# SKAARDUINO_v4.net
KiCad netlist of a schematic drawn in EAGLE
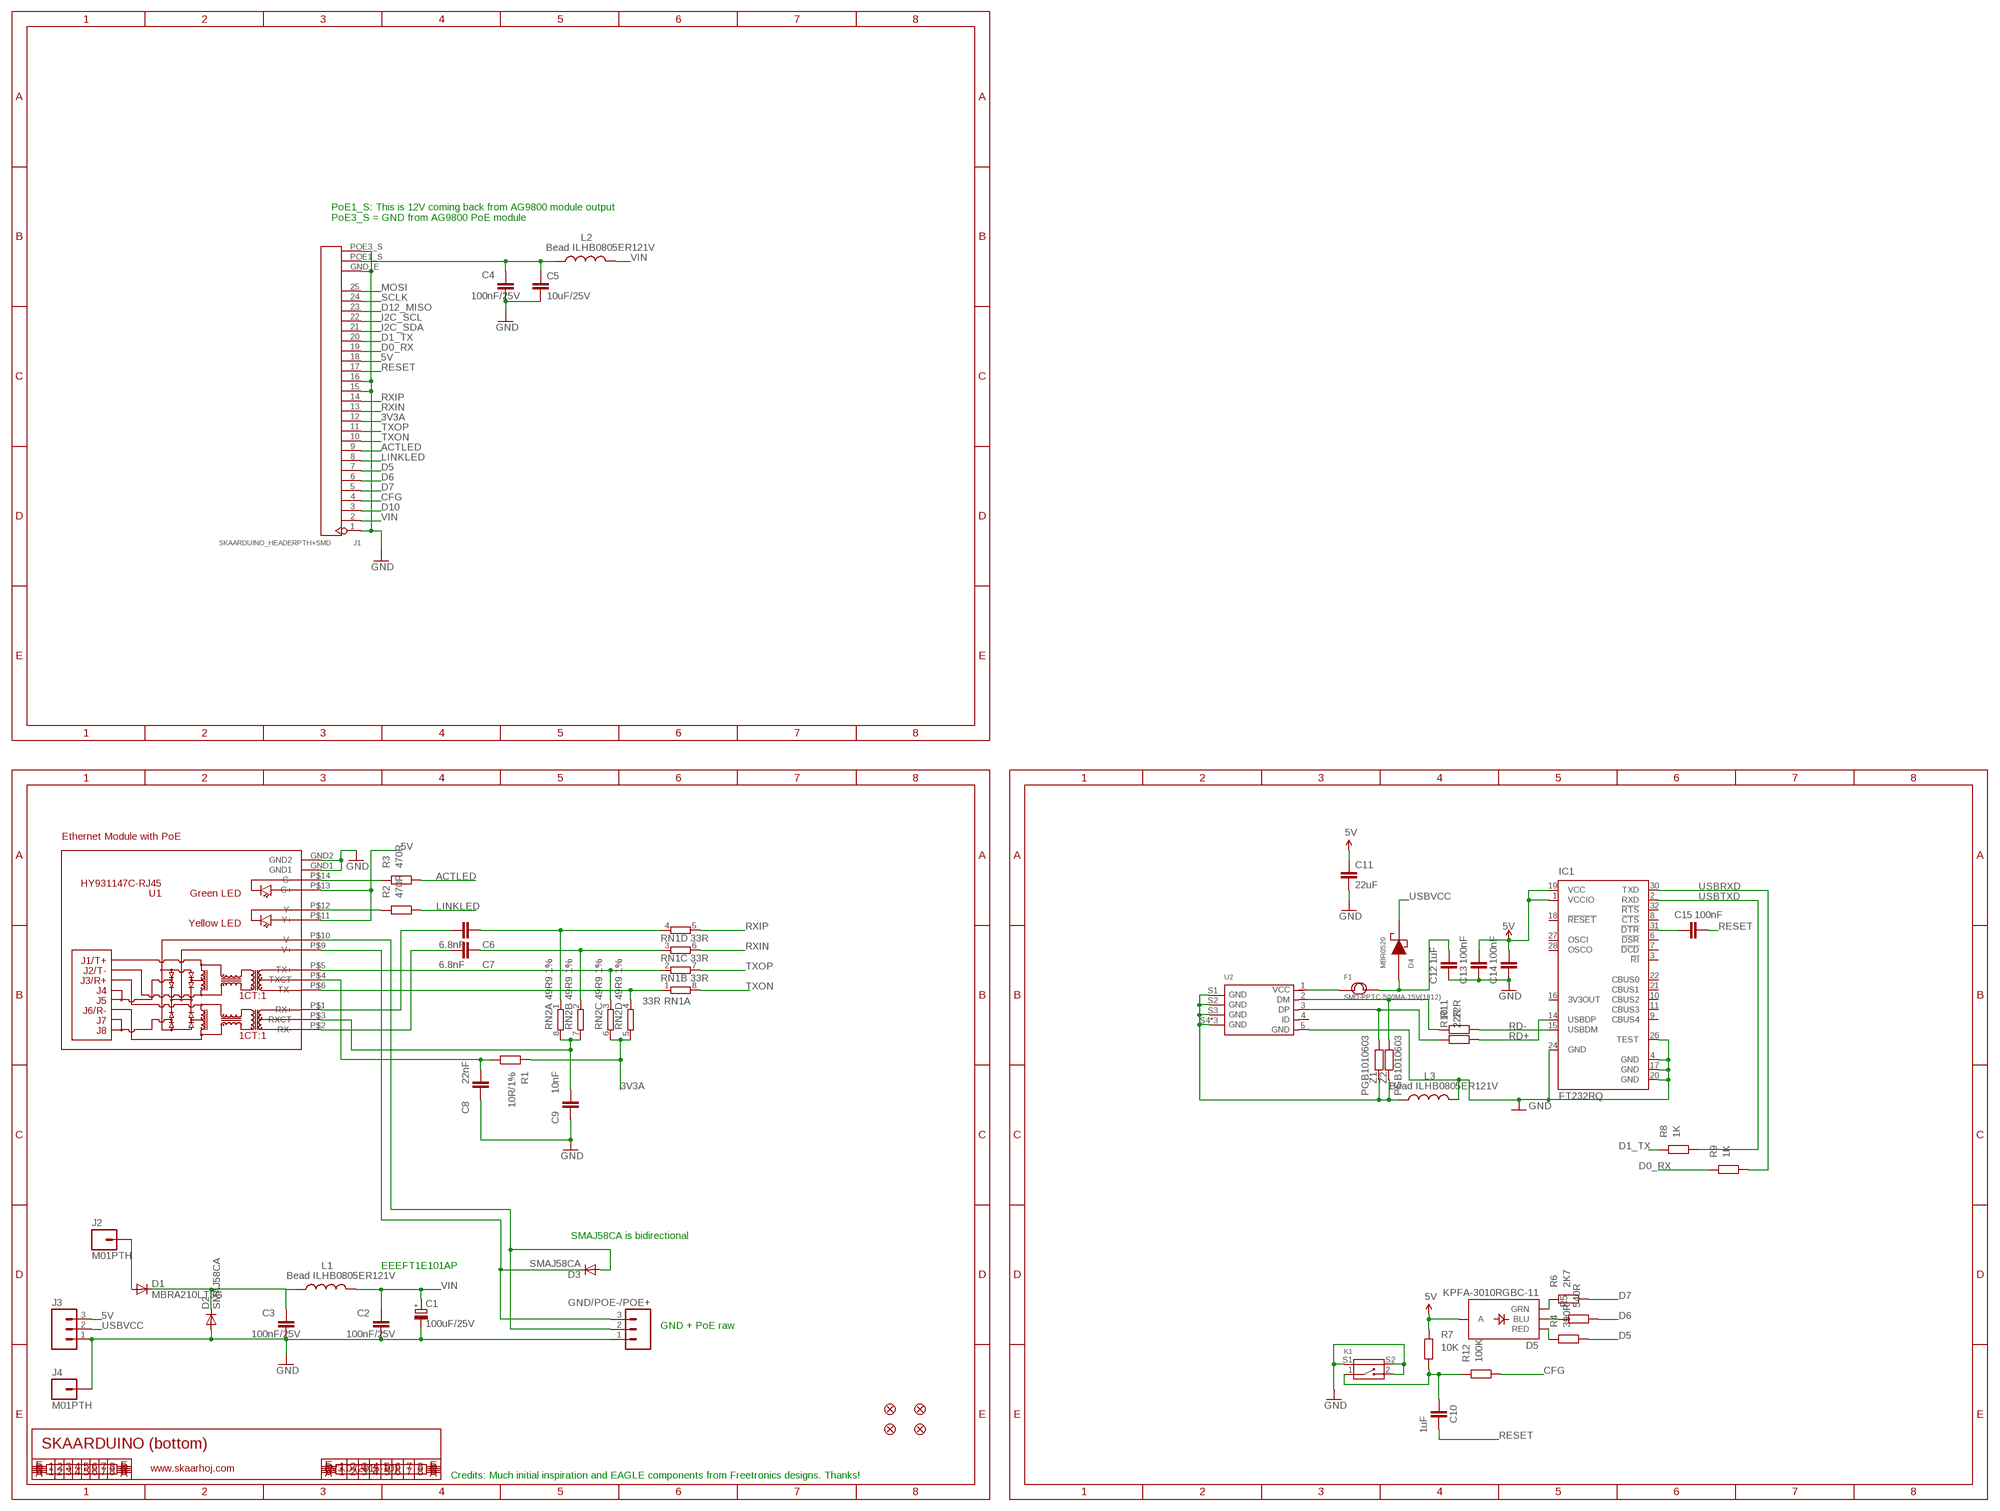
[diagram p0: schematic, sheet 1]
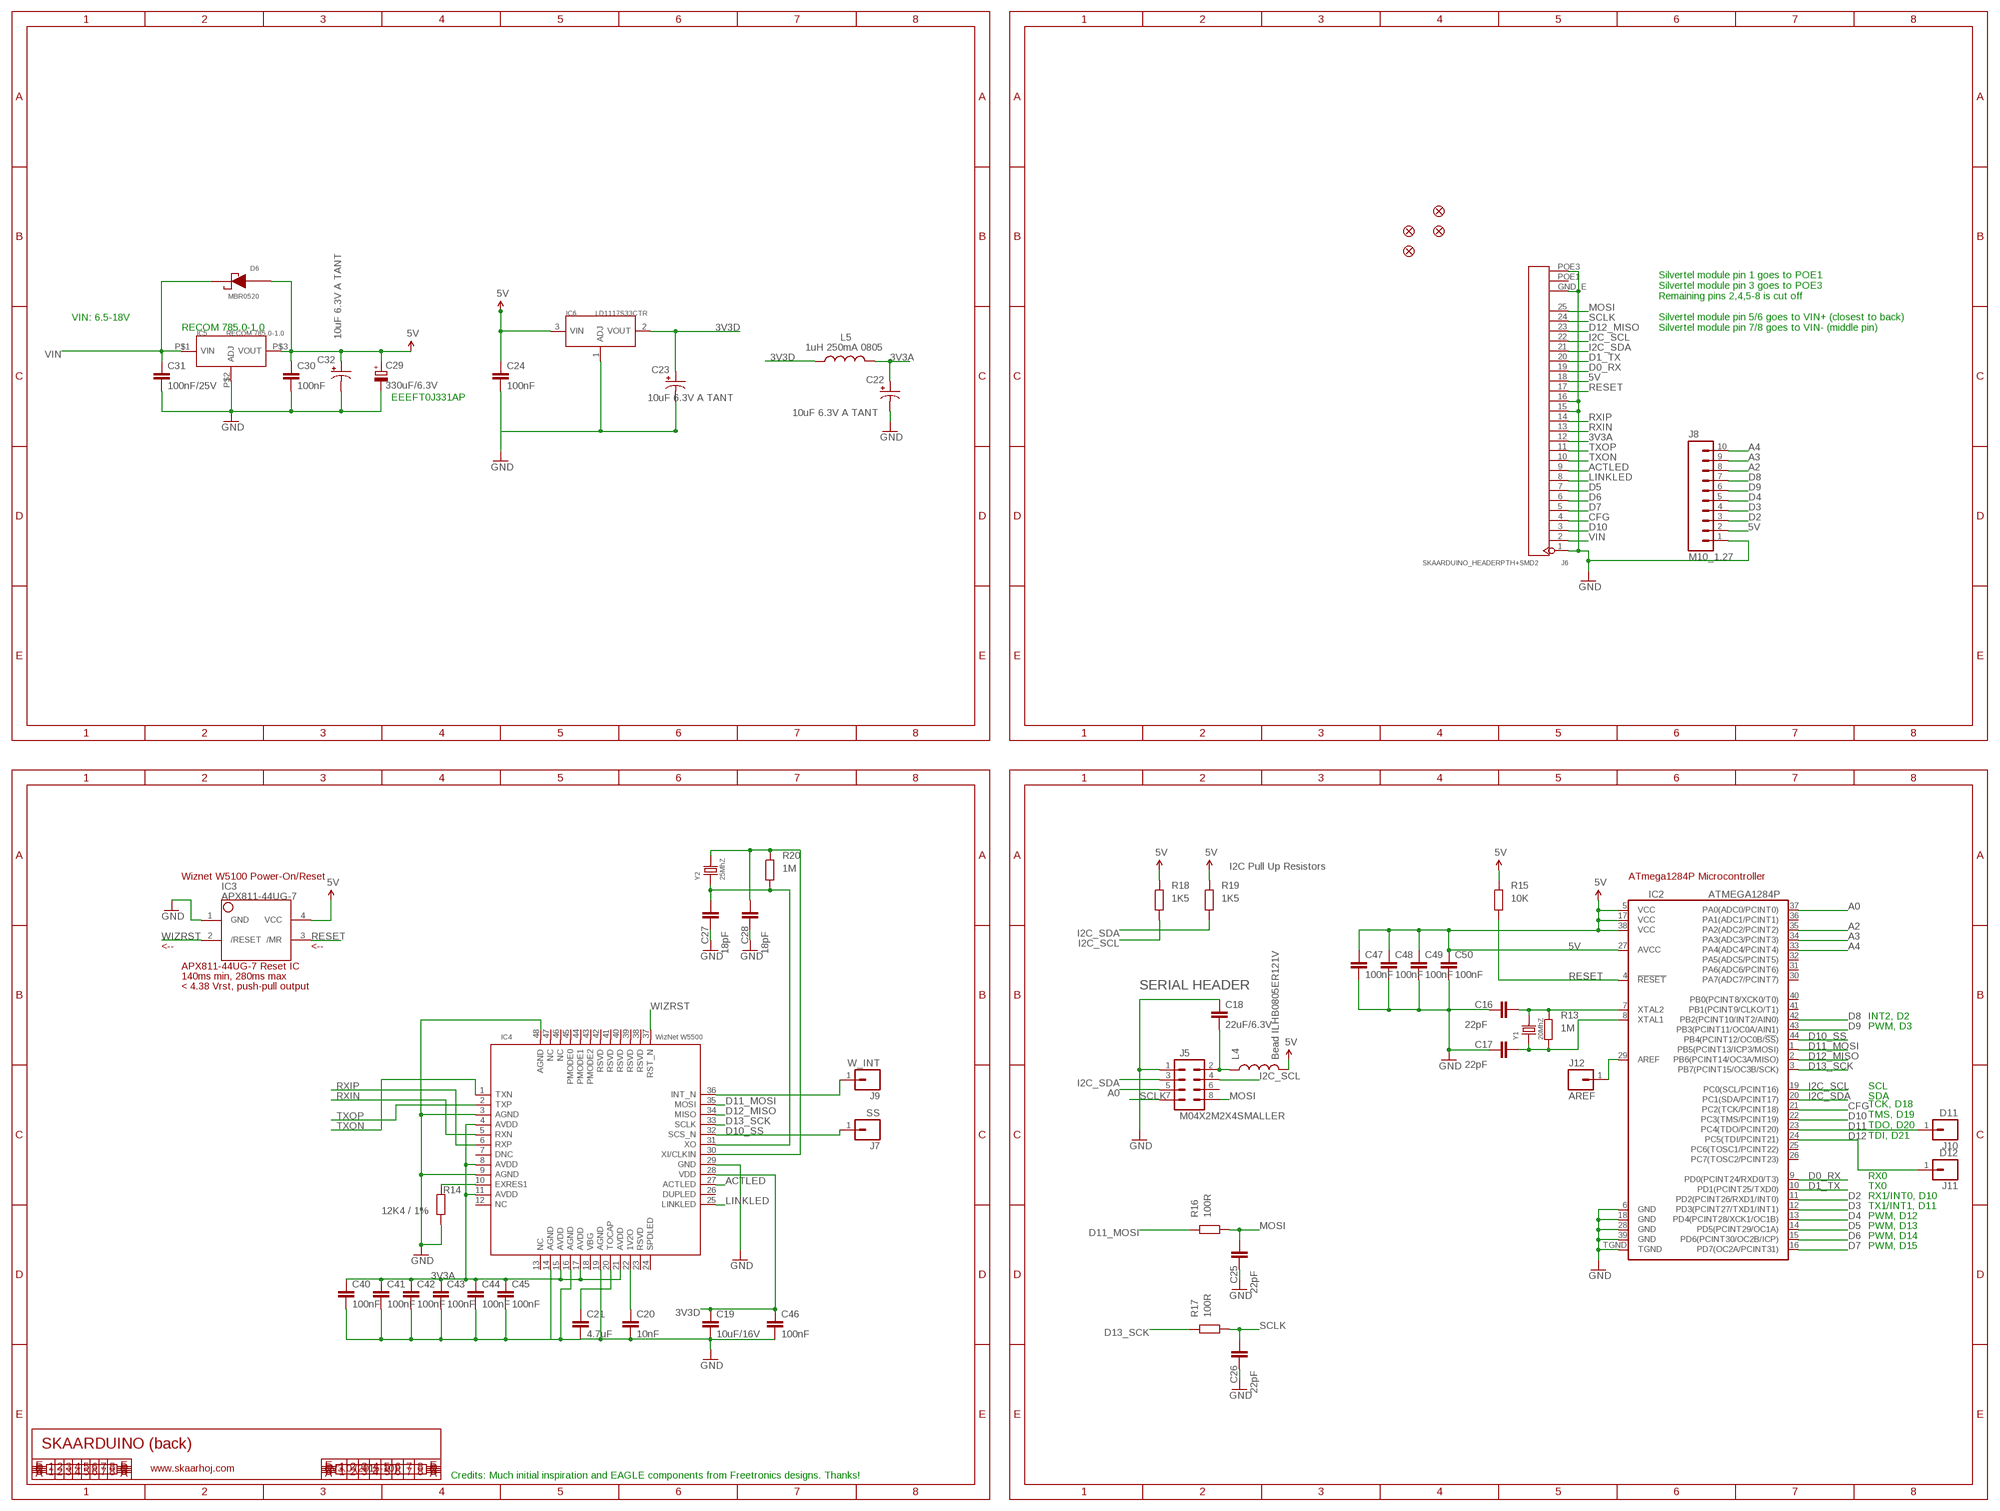
[diagram p1: schematic, sheet 2]

(export (version "E")
  (design (tool "Eeschema 10.0.6"))
  (components
    (comp (ref "C16")
      (value "22pF")
      (footprint "eagle-import:0402C")
      (libsource (lib "eagle-import") (part "C-EU0402C"))
    )
    (comp (ref "C17")
      (value "22pF")
      (footprint "eagle-import:0402C")
      (libsource (lib "eagle-import") (part "C-EU0402C"))
    )
    (comp (ref "C18")
      (value "22uF/6.3V")
      (footprint "eagle-import:0805")
      (libsource (lib "eagle-import") (part "CAP0805"))
    )
    (comp (ref "C19")
      (value "10uF/16V")
      (footprint "eagle-import:0805")
      (libsource (lib "eagle-import") (part "CAP0805"))
    )
    (comp (ref "C20")
      (value "10nF")
      (footprint "eagle-import:0402C")
      (libsource (lib "eagle-import") (part "C-EU0402C"))
    )
    (comp (ref "C21")
      (value "4.7uF")
      (footprint "eagle-import:0805")
      (libsource (lib "eagle-import") (part "CAP0805"))
    )
    (comp (ref "C22")
      (value "10uF 6.3V A TANT")
      (footprint "eagle-import:EIA3216")
      (libsource (lib "eagle-import") (part "CAP_POL1206"))
    )
    (comp (ref "C23")
      (value "10uF 6.3V A TANT")
      (footprint "eagle-import:EIA3216")
      (libsource (lib "eagle-import") (part "CAP_POL1206"))
    )
    (comp (ref "C24")
      (value "100nF")
      (footprint "eagle-import:0402C")
      (libsource (lib "eagle-import") (part "C-EU0402C"))
    )
    (comp (ref "C25")
      (value "22pF")
      (footprint "eagle-import:0402C")
      (libsource (lib "eagle-import") (part "C-EU0402C"))
    )
    (comp (ref "C26")
      (value "22pF")
      (footprint "eagle-import:0402C")
      (libsource (lib "eagle-import") (part "C-EU0402C"))
    )
    (comp (ref "C27")
      (value "18pF")
      (footprint "eagle-import:0402C")
      (libsource (lib "eagle-import") (part "C-EU0402C"))
    )
    (comp (ref "C28")
      (value "18pF")
      (footprint "eagle-import:0402C")
      (libsource (lib "eagle-import") (part "C-EU0402C"))
    )
    (comp (ref "C29")
      (value "330uF/6.3V")
      (footprint "eagle-import:PANASONIC_D")
      (libsource (lib "eagle-import") (part "CPOL-EUD"))
    )
    (comp (ref "C30")
      (value "100nF")
      (footprint "eagle-import:0402C")
      (libsource (lib "eagle-import") (part "C-EU0402C"))
    )
    (comp (ref "C31")
      (value "100nF/25V")
      (footprint "eagle-import:0402C")
      (libsource (lib "eagle-import") (part "C-EU0402C"))
    )
    (comp (ref "C32")
      (value "10uF 6.3V A TANT")
      (footprint "eagle-import:EIA3216")
      (libsource (lib "eagle-import") (part "CAP_POL1206"))
    )
    (comp (ref "C40")
      (value "100nF")
      (footprint "eagle-import:0402C")
      (libsource (lib "eagle-import") (part "C-EU0402C"))
    )
    (comp (ref "C41")
      (value "100nF")
      (footprint "eagle-import:0402C")
      (libsource (lib "eagle-import") (part "C-EU0402C"))
    )
    (comp (ref "C42")
      (value "100nF")
      (footprint "eagle-import:0402C")
      (libsource (lib "eagle-import") (part "C-EU0402C"))
    )
    (comp (ref "C43")
      (value "100nF")
      (footprint "eagle-import:0402C")
      (libsource (lib "eagle-import") (part "C-EU0402C"))
    )
    (comp (ref "C44")
      (value "100nF")
      (footprint "eagle-import:0402C")
      (libsource (lib "eagle-import") (part "C-EU0402C"))
    )
    (comp (ref "C45")
      (value "100nF")
      (footprint "eagle-import:0402C")
      (libsource (lib "eagle-import") (part "C-EU0402C"))
    )
    (comp (ref "C46")
      (value "100nF")
      (footprint "eagle-import:0402C")
      (libsource (lib "eagle-import") (part "C-EU0402C"))
    )
    (comp (ref "C47")
      (value "100nF")
      (footprint "eagle-import:0402C")
      (libsource (lib "eagle-import") (part "C-EU0402C"))
    )
    (comp (ref "C48")
      (value "100nF")
      (footprint "eagle-import:0402C")
      (libsource (lib "eagle-import") (part "C-EU0402C"))
    )
    (comp (ref "C49")
      (value "100nF")
      (footprint "eagle-import:0402C")
      (libsource (lib "eagle-import") (part "C-EU0402C"))
    )
    (comp (ref "C50")
      (value "100nF")
      (footprint "eagle-import:0402C")
      (libsource (lib "eagle-import") (part "C-EU0402C"))
    )
    (comp (ref "D6")
      (value "MBR0520")
      (footprint "eagle-import:SOD-123")
      (libsource (lib "eagle-import") (part "MBR0520"))
    )
    (comp (ref "FID5")
      (value "FIDUCIAL1X2.5")
      (footprint "eagle-import:FIDUCIAL-1X2.5")
      (libsource (lib "eagle-import") (part "FIDUCIAL1X2.5"))
    )
    (comp (ref "FID6")
      (value "FIDUCIAL1X2.5")
      (footprint "eagle-import:FIDUCIAL-1X2.5")
      (libsource (lib "eagle-import") (part "FIDUCIAL1X2.5"))
    )
    (comp (ref "FID7")
      (value "FIDUCIAL1X2.5")
      (footprint "eagle-import:FIDUCIAL-1X2.5")
      (libsource (lib "eagle-import") (part "FIDUCIAL1X2.5"))
    )
    (comp (ref "FID8")
      (value "FIDUCIAL1X2.5")
      (footprint "eagle-import:FIDUCIAL-1X2.5")
      (libsource (lib "eagle-import") (part "FIDUCIAL1X2.5"))
    )
    (comp (ref "IC2")
      (value "ATMEGA1284P")
      (footprint "eagle-import:QFN-44M1")
      (libsource (lib "eagle-import") (part "ATMEGA1284P"))
    )
    (comp (ref "IC3")
      (value "APX811-44UG-7")
      (footprint "eagle-import:SOT143-R")
      (libsource (lib "eagle-import") (part "APX81X-RESET-IC"))
    )
    (comp (ref "IC4")
      (value "WizNet W5500")
      (footprint "eagle-import:LQFP-48")
      (libsource (lib "eagle-import") (part "DRIVER-W5500"))
    )
    (comp (ref "IC5")
      (value "RECOM 785.0-1.0")
      (footprint "eagle-import:RECOM_785.0-1.0")
      (libsource (lib "eagle-import") (part "PMIC-LM317EMP"))
    )
    (comp (ref "IC6")
      (value "LD1117S33CTR")
      (footprint "eagle-import:SOT-223-UPRIGHT")
      (libsource (lib "eagle-import") (part "PMIC-LM317EMPUPRIGHT"))
    )
    (comp (ref "J5")
      (value "M04X2M2X4SMALLER")
      (footprint "eagle-import:M2X4SMALLER")
      (libsource (lib "eagle-import") (part "M04X2M2X4SMALLER"))
    )
    (comp (ref "J6")
      (value "SKAARDUINO_HEADERPTH+SMD2")
      (footprint "eagle-import:SKAARDUINO_PTH_SMD2_HEADER")
      (libsource (lib "eagle-import") (part "SKAARDUINO_HEADERPTH+SMD2"))
    )
    (comp (ref "J7")
      (value "SS")
      (footprint "eagle-import:M1X1")
      (libsource (lib "eagle-import") (part "M1X1TEST"))
    )
    (comp (ref "J8")
      (value "M10_1.27")
      (footprint "eagle-import:M10X1")
      (libsource (lib "eagle-import") (part "M10_1.27"))
    )
    (comp (ref "J9")
      (value "W_INT")
      (footprint "eagle-import:M1X1")
      (libsource (lib "eagle-import") (part "M1X1TEST"))
    )
    (comp (ref "J10")
      (value "D11")
      (footprint "eagle-import:M1X1")
      (libsource (lib "eagle-import") (part "M1X1TEST"))
    )
    (comp (ref "J11")
      (value "D12")
      (footprint "eagle-import:M1X1")
      (libsource (lib "eagle-import") (part "M1X1TEST"))
    )
    (comp (ref "J12")
      (value "AREF")
      (footprint "eagle-import:M1X1")
      (libsource (lib "eagle-import") (part "M1X1TEST"))
    )
    (comp (ref "L4")
      (value "Bead ILHB0805ER121V")
      (footprint "eagle-import:0805")
      (libsource (lib "eagle-import") (part "INDUCTOR0805"))
    )
    (comp (ref "L5")
      (value "1uH 250mA 0805")
      (footprint "eagle-import:L2012C")
      (libsource (lib "eagle-import") (part "L-USL2012C"))
    )
    (comp (ref "R13")
      (value "1M")
      (footprint "eagle-import:0402")
      (libsource (lib "eagle-import") (part "freetronics-jon_RESISTOR0402"))
    )
    (comp (ref "R14")
      (value "12K4 / 1%")
      (footprint "eagle-import:0402")
      (libsource (lib "eagle-import") (part "freetronics-jon_RESISTOR0402"))
    )
    (comp (ref "R15")
      (value "10K")
      (footprint "eagle-import:0402")
      (libsource (lib "eagle-import") (part "freetronics-jon_RESISTOR0402"))
    )
    (comp (ref "R16")
      (value "100R")
      (footprint "eagle-import:0402")
      (libsource (lib "eagle-import") (part "freetronics-jon_RESISTOR0402"))
    )
    (comp (ref "R17")
      (value "100R")
      (footprint "eagle-import:0402")
      (libsource (lib "eagle-import") (part "freetronics-jon_RESISTOR0402"))
    )
    (comp (ref "R18")
      (value "1K5")
      (footprint "eagle-import:0402")
      (libsource (lib "eagle-import") (part "freetronics-jon_RESISTOR0402"))
    )
    (comp (ref "R19")
      (value "1K5")
      (footprint "eagle-import:0402")
      (libsource (lib "eagle-import") (part "freetronics-jon_RESISTOR0402"))
    )
    (comp (ref "R20")
      (value "1M")
      (footprint "eagle-import:0402")
      (libsource (lib "eagle-import") (part "freetronics-jon_RESISTOR0402"))
    )
    (comp (ref "Y1")
      (value "20MhZ")
      (footprint "eagle-import:X2-SMD-5.0X3.2X1.3MM")
      (fields (field (name "MPN") "X053201602002"))
      (libsource (lib "eagle-import") (part "SMD-CRYSTAL-16MHZ-8PF-20PPM-40R(2P-5.0X3.2MM)"))
    )
    (comp (ref "Y2")
      (value "25MhZ")
      (footprint "eagle-import:X2-SMD-5.0X3.2X1.3MM")
      (fields (field (name "MPN") "X053201602002"))
      (libsource (lib "eagle-import") (part "SMD-CRYSTAL-16MHZ-8PF-20PPM-40R(2P-5.0X3.2MM)"))
    )
    (comp (ref "C1")
      (value "100uF/25V")
      (footprint "eagle-import:PANASONIC_D")
      (libsource (lib "eagle-import") (part "CPOL-EUD"))
    )
    (comp (ref "C2")
      (value "100nF/25V")
      (footprint "eagle-import:C0402")
      (libsource (lib "eagle-import") (part "CAP0402"))
    )
    (comp (ref "C3")
      (value "100nF/25V")
      (footprint "eagle-import:C0402")
      (libsource (lib "eagle-import") (part "CAP0402"))
    )
    (comp (ref "C4")
      (value "100nF/25V")
      (footprint "eagle-import:C0402")
      (libsource (lib "eagle-import") (part "CAP0402"))
    )
    (comp (ref "C5")
      (value "10uF/25V")
      (footprint "eagle-import:0805")
      (libsource (lib "eagle-import") (part "CAP0805"))
    )
    (comp (ref "C6")
      (value "6.8nF")
      (footprint "eagle-import:0402C")
      (libsource (lib "eagle-import") (part "C-EU0402C"))
    )
    (comp (ref "C7")
      (value "6.8nF")
      (footprint "eagle-import:0402C")
      (libsource (lib "eagle-import") (part "C-EU0402C"))
    )
    (comp (ref "C8")
      (value "22nF")
      (footprint "eagle-import:0402C")
      (libsource (lib "eagle-import") (part "C-EU0402C"))
    )
    (comp (ref "C9")
      (value "10nF")
      (footprint "eagle-import:0402C")
      (libsource (lib "eagle-import") (part "C-EU0402C"))
    )
    (comp (ref "C10")
      (value "1uF")
      (footprint "eagle-import:0402C")
      (libsource (lib "eagle-import") (part "C-EU0402C"))
    )
    (comp (ref "C11")
      (value "22uF")
      (footprint "eagle-import:0805")
      (libsource (lib "eagle-import") (part "CAP0805"))
    )
    (comp (ref "C12")
      (value "1uF")
      (footprint "eagle-import:0402C")
      (libsource (lib "eagle-import") (part "C-EU0402C"))
    )
    (comp (ref "C13")
      (value "100nF")
      (footprint "eagle-import:0402C")
      (libsource (lib "eagle-import") (part "C-EU0402C"))
    )
    (comp (ref "C14")
      (value "100nF")
      (footprint "eagle-import:0402C")
      (libsource (lib "eagle-import") (part "C-EU0402C"))
    )
    (comp (ref "C15")
      (value "100nF")
      (footprint "eagle-import:0402C")
      (libsource (lib "eagle-import") (part "C-EU0402C"))
    )
    (comp (ref "D1")
      (value "MBRA210LT3G")
      (footprint "eagle-import:SMA-DIODE")
      (libsource (lib "eagle-import") (part "DIODESMA"))
    )
    (comp (ref "D2")
      (value "SMAJ58CA")
      (footprint "eagle-import:SMA-DIODE")
      (libsource (lib "eagle-import") (part "DIODESMA"))
    )
    (comp (ref "D3")
      (value "SMAJ58CA")
      (footprint "eagle-import:SMA-DIODE")
      (libsource (lib "eagle-import") (part "DIODESMA"))
    )
    (comp (ref "D4")
      (value "MBR0520")
      (footprint "eagle-import:SOD-123")
      (libsource (lib "eagle-import") (part "MBR0520"))
    )
    (comp (ref "D5")
      (value "KPFA-3010RGBC-11")
      (footprint "eagle-import:LED-TRICOLOR-SMD")
      (libsource (lib "eagle-import") (part "LED-TRICOLOR"))
    )
    (comp (ref "F1")
      (value "SMD-PPTC-500MA-15V(1812)")
      (footprint "eagle-import:F1812")
      (libsource (lib "eagle-import") (part "SMD-PPTC-500MA-15V(1812)"))
    )
    (comp (ref "FID1")
      (value "FIDUCIAL1X2.5")
      (footprint "eagle-import:FIDUCIAL-1X2.5")
      (libsource (lib "eagle-import") (part "FIDUCIAL1X2.5"))
    )
    (comp (ref "FID2")
      (value "FIDUCIAL1X2.5")
      (footprint "eagle-import:FIDUCIAL-1X2.5")
      (libsource (lib "eagle-import") (part "FIDUCIAL1X2.5"))
    )
    (comp (ref "FID3")
      (value "FIDUCIAL1X2.5")
      (footprint "eagle-import:FIDUCIAL-1X2.5")
      (libsource (lib "eagle-import") (part "FIDUCIAL1X2.5"))
    )
    (comp (ref "FID4")
      (value "FIDUCIAL1X2.5")
      (footprint "eagle-import:FIDUCIAL-1X2.5")
      (libsource (lib "eagle-import") (part "FIDUCIAL1X2.5"))
    )
    (comp (ref "GND/POE-/POE+")
      (value "M03LOCK")
      (footprint "eagle-import:1X03_LOCK")
      (libsource (lib "eagle-import") (part "M03LOCK"))
    )
    (comp (ref "IC1")
      (value "FT232RQ")
      (footprint "eagle-import:QFN32")
      (libsource (lib "eagle-import") (part "FT232RQ"))
    )
    (comp (ref "J1")
      (value "SKAARDUINO_HEADERPTH+SMD")
      (footprint "eagle-import:SKAARDUINO_PTH_SMD_HEADER")
      (libsource (lib "eagle-import") (part "SKAARDUINO_HEADERPTH+SMD"))
    )
    (comp (ref "J2")
      (value "M01PTH")
      (footprint "eagle-import:1X01")
      (libsource (lib "eagle-import") (part "M01PTH"))
    )
    (comp (ref "J3")
      (value "M03LOCK")
      (footprint "eagle-import:1X03_LOCK")
      (libsource (lib "eagle-import") (part "M03LOCK"))
    )
    (comp (ref "J4")
      (value "M01PTH")
      (footprint "eagle-import:1X01")
      (libsource (lib "eagle-import") (part "M01PTH"))
    )
    (comp (ref "K1")
      (value "SMD-BUTTON-2+2P")
      (footprint "eagle-import:SW4-SMD-7.0X3.5X3.5MM-90D")
      (fields (field (name "MPN") "TS-1188E"))
      (libsource (lib "eagle-import") (part "SMD-BUTTON-2+2P"))
    )
    (comp (ref "L1")
      (value "Bead ILHB0805ER121V")
      (footprint "eagle-import:L2012C")
      (libsource (lib "eagle-import") (part "L-USL2012C"))
    )
    (comp (ref "L2")
      (value "Bead ILHB0805ER121V")
      (footprint "eagle-import:L2012C")
      (libsource (lib "eagle-import") (part "L-USL2012C"))
    )
    (comp (ref "L3")
      (value "Bead ILHB0805ER121V")
      (footprint "eagle-import:L2012C")
      (libsource (lib "eagle-import") (part "L-USL2012C"))
    )
    (comp (ref "R1")
      (value "10R/1%")
      (footprint "eagle-import:0402")
      (libsource (lib "eagle-import") (part "freetronics-jon_RESISTOR0402"))
    )
    (comp (ref "R2")
      (value "470R")
      (footprint "eagle-import:0402")
      (libsource (lib "eagle-import") (part "freetronics-jon_RESISTOR0402"))
    )
    (comp (ref "R3")
      (value "470R")
      (footprint "eagle-import:0402")
      (libsource (lib "eagle-import") (part "freetronics-jon_RESISTOR0402"))
    )
    (comp (ref "R4")
      (value "390R")
      (footprint "eagle-import:0402")
      (libsource (lib "eagle-import") (part "freetronics-jon_RESISTOR0402"))
    )
    (comp (ref "R5")
      (value "540R")
      (footprint "eagle-import:0402")
      (libsource (lib "eagle-import") (part "freetronics-jon_RESISTOR0402"))
    )
    (comp (ref "R6")
      (value "2K7")
      (footprint "eagle-import:0402")
      (libsource (lib "eagle-import") (part "freetronics-jon_RESISTOR0402"))
    )
    (comp (ref "R7")
      (value "10K")
      (footprint "eagle-import:0402")
      (libsource (lib "eagle-import") (part "freetronics-jon_RESISTOR0402"))
    )
    (comp (ref "R8")
      (value "1K")
      (footprint "eagle-import:0402")
      (libsource (lib "eagle-import") (part "freetronics-jon_RESISTOR0402"))
    )
    (comp (ref "R9")
      (value "1K")
      (footprint "eagle-import:0402")
      (libsource (lib "eagle-import") (part "freetronics-jon_RESISTOR0402"))
    )
    (comp (ref "R10")
      (value "22R")
      (footprint "eagle-import:0402")
      (libsource (lib "eagle-import") (part "freetronics-jon_RESISTOR0402"))
    )
    (comp (ref "R11")
      (value "22R")
      (footprint "eagle-import:0402")
      (libsource (lib "eagle-import") (part "freetronics-jon_RESISTOR0402"))
    )
    (comp (ref "R12")
      (value "100K")
      (footprint "eagle-import:0402")
      (libsource (lib "eagle-import") (part "freetronics-jon_RESISTOR0402"))
    )
    (comp (ref "RN1")
      (value "33R")
      (footprint "eagle-import:CAY16")
      (libsource (lib "eagle-import") (part "4R-NCAY16"))
    )
    (comp (ref "RN2")
      (value "49R9 1%")
      (footprint "eagle-import:CAY16")
      (libsource (lib "eagle-import") (part "4R-NCAY16"))
    )
    (comp (ref "U1")
      (value "HY931147C-RJ45")
      (footprint "eagle-import:HY931147C")
      (libsource (lib "eagle-import") (part "HY931147C-RJ45"))
    )
    (comp (ref "U2")
      (value "MICRO-USB-SMD-B-WITHOUT-POST-W/P(ST-USB-001G)")
      (footprint "eagle-import:MICRO-USB5+4P-SMD-0.65-B")
      (fields (field (name "MPN") "ST-USB-001G"))
      (libsource (lib "eagle-import") (part "MICRO-USB-SMD-B-WITHOUT-POST-W/P(ST-USB-001G)"))
    )
    (comp (ref "Z1")
      (value "PGB1010603")
      (footprint "eagle-import:C0402")
      (libsource (lib "eagle-import") (part "RESISTOR0402"))
    )
    (comp (ref "Z2")
      (value "PGB1010603")
      (footprint "eagle-import:C0402")
      (libsource (lib "eagle-import") (part "RESISTOR0402"))
    )
  )
  (nets
    (net (code "1") (name "3V3A") (class "Default")
      (node (ref "C22") (pin "A") (pinfunction "+_A") (pintype "passive"))
      (node (ref "C40") (pin "1") (pinfunction "1_1") (pintype "passive"))
      (node (ref "C41") (pin "1") (pinfunction "1_1") (pintype "passive"))
      (node (ref "C42") (pin "1") (pinfunction "1_1") (pintype "passive"))
      (node (ref "C43") (pin "1") (pinfunction "1_1") (pintype "passive"))
      (node (ref "C44") (pin "1") (pinfunction "1_1") (pintype "passive"))
      (node (ref "C45") (pin "1") (pinfunction "1_1") (pintype "passive"))
      (node (ref "IC4") (pin "11") (pinfunction "AVDD_11") (pintype "passive"))
      (node (ref "IC4") (pin "15") (pinfunction "AVDD_15") (pintype "passive"))
      (node (ref "IC4") (pin "17") (pinfunction "AVDD_17") (pintype "passive"))
      (node (ref "IC4") (pin "21") (pinfunction "AVDD_21") (pintype "passive"))
      (node (ref "IC4") (pin "4") (pinfunction "AVDD_4") (pintype "passive"))
      (node (ref "IC4") (pin "8") (pinfunction "AVDD_8") (pintype "passive"))
      (node (ref "J1") (pin "12") (pinfunction "12_12") (pintype "bidirectional"))
      (node (ref "J6") (pin "12") (pinfunction "12_12") (pintype "bidirectional"))
      (node (ref "L5") (pin "2") (pinfunction "2_2") (pintype "passive"))
      (node (ref "R1") (pin "2") (pinfunction "2_2") (pintype "passive"))
      (node (ref "RN2") (pin "5") (pinfunction "2_5") (pintype "passive"))
      (node (ref "RN2") (pin "6") (pinfunction "2_6") (pintype "passive"))
    )
    (net (code "2") (name "3V3D") (class "Default")
      (node (ref "C19") (pin "1") (pinfunction "1_1") (pintype "passive"))
      (node (ref "C23") (pin "A") (pinfunction "+_A") (pintype "passive"))
      (node (ref "C46") (pin "1") (pinfunction "1_1") (pintype "passive"))
      (node (ref "IC4") (pin "28") (pinfunction "VDD_28") (pintype "passive"))
      (node (ref "IC6") (pin "2") (pinfunction "VOUT_2") (pintype "bidirectional"))
      (node (ref "L5") (pin "1") (pinfunction "1_1") (pintype "passive"))
    )
    (net (code "3") (name "5V") (class "Default")
      (node (ref "C11") (pin "1") (pinfunction "1_1") (pintype "passive"))
      (node (ref "C13") (pin "2") (pinfunction "2_2") (pintype "passive"))
      (node (ref "C14") (pin "2") (pinfunction "2_2") (pintype "passive"))
      (node (ref "C24") (pin "1") (pinfunction "1_1") (pintype "passive"))
      (node (ref "C29") (pin "+") (pinfunction "+_+") (pintype "passive"))
      (node (ref "C30") (pin "1") (pinfunction "1_1") (pintype "passive"))
      (node (ref "C32") (pin "A") (pinfunction "+_A") (pintype "passive"))
      (node (ref "C47") (pin "1") (pinfunction "1_1") (pintype "passive"))
      (node (ref "C48") (pin "1") (pinfunction "1_1") (pintype "passive"))
      (node (ref "C49") (pin "1") (pinfunction "1_1") (pintype "passive"))
      (node (ref "C50") (pin "1") (pinfunction "1_1") (pintype "passive"))
      (node (ref "D5") (pin "A") (pinfunction "A_A") (pintype "bidirectional"))
      (node (ref "D6") (pin "2") (pinfunction "AN_2") (pintype "passive"))
      (node (ref "IC1") (pin "1") (pinfunction "VCCIO_1") (pintype "power_in"))
      (node (ref "IC1") (pin "19") (pinfunction "VCC_19") (pintype "power_in"))
      (node (ref "IC2") (pin "17") (pinfunction "VCC_17") (pintype "bidirectional"))
      (node (ref "IC2") (pin "27") (pinfunction "AVCC_27") (pintype "bidirectional"))
      (node (ref "IC2") (pin "38") (pinfunction "VCC_38") (pintype "bidirectional"))
      (node (ref "IC2") (pin "5") (pinfunction "VCC_5") (pintype "bidirectional"))
      (node (ref "IC3") (pin "4") (pinfunction "VCC_4") (pintype "power_in"))
      (node (ref "IC5") (pin "P$3") (pinfunction "VOUT_P$3") (pintype "bidirectional"))
      (node (ref "IC6") (pin "3") (pinfunction "VIN_3") (pintype "bidirectional"))
      (node (ref "J1") (pin "18") (pinfunction "18_18") (pintype "bidirectional"))
      (node (ref "J3") (pin "3") (pinfunction "3_3") (pintype "passive"))
      (node (ref "J6") (pin "18") (pinfunction "18_18") (pintype "bidirectional"))
      (node (ref "J8") (pin "2") (pinfunction "2_2") (pintype "passive"))
      (node (ref "L4") (pin "2") (pinfunction "2_2") (pintype "passive"))
      (node (ref "R15") (pin "2") (pinfunction "2_2") (pintype "passive"))
      (node (ref "R18") (pin "2") (pinfunction "2_2") (pintype "passive"))
      (node (ref "R19") (pin "2") (pinfunction "2_2") (pintype "passive"))
      (node (ref "R7") (pin "2") (pinfunction "2_2") (pintype "passive"))
      (node (ref "U1") (pin "P$11") (pinfunction "Y+_P$11") (pintype "bidirectional"))
      (node (ref "U1") (pin "P$13") (pinfunction "G+_P$13") (pintype "bidirectional"))
    )
    (net (code "4") (name "A0") (class "Default")
      (node (ref "IC2") (pin "37") (pinfunction "PA0(ADC0/PCINT0)_37") (pintype "bidirectional"))
      (node (ref "J5") (pin "5") (pinfunction "5_5") (pintype "passive"))
    )
    (net (code "5") (name "A2") (class "Default")
      (node (ref "IC2") (pin "35") (pinfunction "PA2(ADC2/PCINT2)_35") (pintype "bidirectional"))
      (node (ref "J8") (pin "8") (pinfunction "8_8") (pintype "passive"))
    )
    (net (code "6") (name "A3") (class "Default")
      (node (ref "IC2") (pin "34") (pinfunction "PA3(ADC3/PCINT3)_34") (pintype "bidirectional"))
      (node (ref "J8") (pin "9") (pinfunction "9_9") (pintype "passive"))
    )
    (net (code "7") (name "A4") (class "Default")
      (node (ref "IC2") (pin "33") (pinfunction "PA4(ADC4/PCINT4)_33") (pintype "bidirectional"))
      (node (ref "J8") (pin "10") (pinfunction "10_10") (pintype "passive"))
    )
    (net (code "8") (name "ACTLED") (class "Default")
      (node (ref "IC4") (pin "27") (pinfunction "ACTLED_27") (pintype "passive"))
      (node (ref "J1") (pin "9") (pinfunction "9_9") (pintype "bidirectional"))
      (node (ref "J6") (pin "9") (pinfunction "9_9") (pintype "bidirectional"))
      (node (ref "R3") (pin "1") (pinfunction "1_1") (pintype "passive"))
    )
    (net (code "9") (name "CFG") (class "Default")
      (node (ref "IC2") (pin "21") (pinfunction "PC2(TCK/PCINT18)_21") (pintype "bidirectional"))
      (node (ref "J1") (pin "4") (pinfunction "4_4") (pintype "bidirectional"))
      (node (ref "J6") (pin "4") (pinfunction "4_4") (pintype "bidirectional"))
      (node (ref "R12") (pin "1") (pinfunction "1_1") (pintype "passive"))
    )
    (net (code "10") (name "D0_RX") (class "Default")
      (node (ref "IC2") (pin "9") (pinfunction "PD0(PCINT24/RXD0/T3)_9") (pintype "bidirectional"))
      (node (ref "J1") (pin "19") (pinfunction "19_19") (pintype "bidirectional"))
      (node (ref "J6") (pin "19") (pinfunction "19_19") (pintype "bidirectional"))
      (node (ref "R9") (pin "2") (pinfunction "2_2") (pintype "passive"))
    )
    (net (code "11") (name "D1_TX") (class "Default")
      (node (ref "IC2") (pin "10") (pinfunction "PD1(PCINT25/TXD0)_10") (pintype "bidirectional"))
      (node (ref "J1") (pin "20") (pinfunction "20_20") (pintype "bidirectional"))
      (node (ref "J6") (pin "20") (pinfunction "20_20") (pintype "bidirectional"))
      (node (ref "R8") (pin "2") (pinfunction "2_2") (pintype "passive"))
    )
    (net (code "12") (name "D2") (class "Default")
      (node (ref "IC2") (pin "11") (pinfunction "PD2(PCINT26/RXD1/INT0)_11") (pintype "bidirectional"))
      (node (ref "J8") (pin "3") (pinfunction "3_3") (pintype "passive"))
    )
    (net (code "13") (name "D3") (class "Default")
      (node (ref "IC2") (pin "12") (pinfunction "PD3(PCINT27/TXD1/INT1)_12") (pintype "bidirectional"))
      (node (ref "J8") (pin "4") (pinfunction "4_4") (pintype "passive"))
    )
    (net (code "14") (name "D4") (class "Default")
      (node (ref "IC2") (pin "13") (pinfunction "PD4(PCINT28/XCK1/OC1B)_13") (pintype "bidirectional"))
      (node (ref "J8") (pin "5") (pinfunction "5_5") (pintype "passive"))
    )
    (net (code "15") (name "D5") (class "Default")
      (node (ref "IC2") (pin "14") (pinfunction "PD5(PCINT29/OC1A)_14") (pintype "bidirectional"))
      (node (ref "J1") (pin "7") (pinfunction "7_7") (pintype "bidirectional"))
      (node (ref "J6") (pin "7") (pinfunction "7_7") (pintype "bidirectional"))
      (node (ref "R4") (pin "1") (pinfunction "1_1") (pintype "passive"))
    )
    (net (code "16") (name "D6") (class "Default")
      (node (ref "IC2") (pin "15") (pinfunction "PD6(PCINT30/OC2B/ICP)_15") (pintype "bidirectional"))
      (node (ref "J1") (pin "6") (pinfunction "6_6") (pintype "bidirectional"))
      (node (ref "J6") (pin "6") (pinfunction "6_6") (pintype "bidirectional"))
      (node (ref "R5") (pin "1") (pinfunction "1_1") (pintype "passive"))
    )
    (net (code "17") (name "D7") (class "Default")
      (node (ref "IC2") (pin "16") (pinfunction "PD7(OC2A/PCINT31)_16") (pintype "bidirectional"))
      (node (ref "J1") (pin "5") (pinfunction "5_5") (pintype "bidirectional"))
      (node (ref "J6") (pin "5") (pinfunction "5_5") (pintype "bidirectional"))
      (node (ref "R6") (pin "1") (pinfunction "1_1") (pintype "passive"))
    )
    (net (code "18") (name "D8") (class "Default")
      (node (ref "IC2") (pin "42") (pinfunction "PB2(PCINT10/INT2/AIN0)_42") (pintype "bidirectional"))
      (node (ref "J8") (pin "7") (pinfunction "7_7") (pintype "passive"))
    )
    (net (code "19") (name "D9") (class "Default")
      (node (ref "IC2") (pin "43") (pinfunction "PB3(PCINT11/OC0A/AIN1)_43") (pintype "bidirectional"))
      (node (ref "J8") (pin "6") (pinfunction "6_6") (pintype "passive"))
    )
    (net (code "20") (name "D10") (class "Default")
      (node (ref "IC2") (pin "22") (pinfunction "PC3(TMS/PCINT19)_22") (pintype "bidirectional"))
      (node (ref "J1") (pin "3") (pinfunction "3_3") (pintype "bidirectional"))
      (node (ref "J6") (pin "3") (pinfunction "3_3") (pintype "bidirectional"))
    )
    (net (code "21") (name "D10_SS") (class "Default")
      (node (ref "IC2") (pin "44") (pinfunction "PB4(PCINT12/OC0B/~{SS})_44") (pintype "bidirectional"))
      (node (ref "IC4") (pin "32") (pinfunction "SCS_N_32") (pintype "passive"))
      (node (ref "J7") (pin "1") (pinfunction "5_1") (pintype "passive"))
    )
    (net (code "22") (name "D11") (class "Default")
      (node (ref "IC2") (pin "23") (pinfunction "PC4(TDO/PCINT20)_23") (pintype "bidirectional"))
      (node (ref "J10") (pin "1") (pinfunction "5_1") (pintype "passive"))
    )
    (net (code "23") (name "D11_MOSI") (class "Default")
      (node (ref "IC2") (pin "1") (pinfunction "PB5(PCINT13/ICP3/MOSI)_1") (pintype "bidirectional"))
      (node (ref "IC4") (pin "35") (pinfunction "MOSI_35") (pintype "passive"))
      (node (ref "R16") (pin "2") (pinfunction "2_2") (pintype "passive"))
    )
    (net (code "24") (name "D12") (class "Default")
      (node (ref "IC2") (pin "24") (pinfunction "PC5(TDI/PCINT21)_24") (pintype "bidirectional"))
      (node (ref "J11") (pin "1") (pinfunction "5_1") (pintype "passive"))
    )
    (net (code "25") (name "D12_MISO") (class "Default")
      (node (ref "IC2") (pin "2") (pinfunction "PB6(PCINT14/OC3A/MISO)_2") (pintype "bidirectional"))
      (node (ref "IC4") (pin "34") (pinfunction "MISO_34") (pintype "passive"))
      (node (ref "J1") (pin "23") (pinfunction "23_23") (pintype "bidirectional"))
      (node (ref "J6") (pin "23") (pinfunction "23_23") (pintype "bidirectional"))
    )
    (net (code "26") (name "D13_SCK") (class "Default")
      (node (ref "IC2") (pin "3") (pinfunction "PB7(PCINT15/OC3B/SCK)_3") (pintype "bidirectional"))
      (node (ref "IC4") (pin "33") (pinfunction "SCLK_33") (pintype "passive"))
      (node (ref "R17") (pin "2") (pinfunction "2_2") (pintype "passive"))
    )
    (net (code "27") (name "GND") (class "Default")
      (node (ref "C1") (pin "-") (pinfunction "-_-") (pintype "passive"))
      (node (ref "C11") (pin "2") (pinfunction "2_2") (pintype "passive"))
      (node (ref "C12") (pin "1") (pinfunction "1_1") (pintype "passive"))
      (node (ref "C13") (pin "1") (pinfunction "1_1") (pintype "passive"))
      (node (ref "C14") (pin "1") (pinfunction "1_1") (pintype "passive"))
      (node (ref "C16") (pin "1") (pinfunction "1_1") (pintype "passive"))
      (node (ref "C17") (pin "1") (pinfunction "1_1") (pintype "passive"))
      (node (ref "C18") (pin "1") (pinfunction "1_1") (pintype "passive"))
      (node (ref "C19") (pin "2") (pinfunction "2_2") (pintype "passive"))
      (node (ref "C2") (pin "2") (pinfunction "2_2") (pintype "passive"))
      (node (ref "C20") (pin "2") (pinfunction "2_2") (pintype "passive"))
      (node (ref "C21") (pin "2") (pinfunction "2_2") (pintype "passive"))
      (node (ref "C22") (pin "C") (pinfunction "-_C") (pintype "passive"))
      (node (ref "C23") (pin "C") (pinfunction "-_C") (pintype "passive"))
      (node (ref "C24") (pin "2") (pinfunction "2_2") (pintype "passive"))
      (node (ref "C25") (pin "1") (pinfunction "1_1") (pintype "passive"))
      (node (ref "C26") (pin "1") (pinfunction "1_1") (pintype "passive"))
      (node (ref "C27") (pin "1") (pinfunction "1_1") (pintype "passive"))
      (node (ref "C28") (pin "1") (pinfunction "1_1") (pintype "passive"))
      (node (ref "C29") (pin "-") (pinfunction "-_-") (pintype "passive"))
      (node (ref "C3") (pin "2") (pinfunction "2_2") (pintype "passive"))
      (node (ref "C30") (pin "2") (pinfunction "2_2") (pintype "passive"))
      (node (ref "C31") (pin "2") (pinfunction "2_2") (pintype "passive"))
      (node (ref "C32") (pin "C") (pinfunction "-_C") (pintype "passive"))
      (node (ref "C4") (pin "2") (pinfunction "2_2") (pintype "passive"))
      (node (ref "C40") (pin "2") (pinfunction "2_2") (pintype "passive"))
      (node (ref "C41") (pin "2") (pinfunction "2_2") (pintype "passive"))
      (node (ref "C42") (pin "2") (pinfunction "2_2") (pintype "passive"))
      (node (ref "C43") (pin "2") (pinfunction "2_2") (pintype "passive"))
      (node (ref "C44") (pin "2") (pinfunction "2_2") (pintype "passive"))
      (node (ref "C45") (pin "2") (pinfunction "2_2") (pintype "passive"))
      (node (ref "C46") (pin "2") (pinfunction "2_2") (pintype "passive"))
      (node (ref "C47") (pin "2") (pinfunction "2_2") (pintype "passive"))
      (node (ref "C48") (pin "2") (pinfunction "2_2") (pintype "passive"))
      (node (ref "C49") (pin "2") (pinfunction "2_2") (pintype "passive"))
      (node (ref "C5") (pin "2") (pinfunction "2_2") (pintype "passive"))
      (node (ref "C50") (pin "2") (pinfunction "2_2") (pintype "passive"))
      (node (ref "C8") (pin "1") (pinfunction "1_1") (pintype "passive"))
      (node (ref "C9") (pin "1") (pinfunction "1_1") (pintype "passive"))
      (node (ref "D2") (pin "A") (pinfunction "A_A") (pintype "passive"))
      (node (ref "GND/POE-/POE+") (pin "1") (pinfunction "1_1") (pintype "passive"))
      (node (ref "IC1") (pin "17") (pinfunction "GND_17") (pintype "power_in"))
      (node (ref "IC1") (pin "20") (pinfunction "GND_20") (pintype "power_in"))
      (node (ref "IC1") (pin "24") (pinfunction "GND_24") (pintype "power_in"))
      (node (ref "IC1") (pin "26") (pinfunction "TEST_26") (pintype "input"))
      (node (ref "IC1") (pin "4") (pinfunction "GND_4") (pintype "power_in"))
      (node (ref "IC2") (pin "18") (pinfunction "GND_18") (pintype "bidirectional"))
      (node (ref "IC2") (pin "28") (pinfunction "GND_28") (pintype "bidirectional"))
      (node (ref "IC2") (pin "39") (pinfunction "GND_39") (pintype "bidirectional"))
      (node (ref "IC2") (pin "6") (pinfunction "GND_6") (pintype "bidirectional"))
      (node (ref "IC2") (pin "TGND") (pinfunction "TGND_TGND") (pintype "bidirectional"))
      (node (ref "IC3") (pin "1") (pinfunction "GND_1") (pintype "power_in"))
      (node (ref "IC4") (pin "14") (pinfunction "AGND_14") (pintype "passive"))
      (node (ref "IC4") (pin "16") (pinfunction "AGND_16") (pintype "passive"))
      (node (ref "IC4") (pin "19") (pinfunction "AGND_19") (pintype "passive"))
      (node (ref "IC4") (pin "29") (pinfunction "GND_29") (pintype "passive"))
      (node (ref "IC4") (pin "3") (pinfunction "AGND_3") (pintype "passive"))
      (node (ref "IC4") (pin "48") (pinfunction "AGND_48") (pintype "passive"))
      (node (ref "IC4") (pin "9") (pinfunction "AGND_9") (pintype "passive"))
      (node (ref "IC5") (pin "P$2") (pinfunction "ADJ_P$2") (pintype "bidirectional"))
      (node (ref "IC6") (pin "1") (pinfunction "ADJ_1") (pintype "bidirectional"))
      (node (ref "J1") (pin "1") (pinfunction "1_1") (pintype "bidirectional"))
      (node (ref "J1") (pin "15") (pinfunction "15_15") (pintype "bidirectional"))
      (node (ref "J1") (pin "16") (pinfunction "16_16") (pintype "bidirectional"))
      (node (ref "J1") (pin "GND_E") (pinfunction "26_GND_E") (pintype "bidirectional"))
      (node (ref "J1") (pin "POE3_S") (pinfunction "28_POE3_S") (pintype "bidirectional"))
      (node (ref "J3") (pin "1") (pinfunction "1_1") (pintype "passive"))
      (node (ref "J4") (pin "1") (pinfunction "1_1") (pintype "passive"))
      (node (ref "J5") (pin "1") (pinfunction "1_1") (pintype "passive"))
      (node (ref "J6") (pin "1") (pinfunction "1_1") (pintype "bidirectional"))
      (node (ref "J6") (pin "15") (pinfunction "15_15") (pintype "bidirectional"))
      (node (ref "J6") (pin "16") (pinfunction "16_16") (pintype "bidirectional"))
      (node (ref "J6") (pin "GND_E") (pinfunction "26_GND_E") (pintype "bidirectional"))
      (node (ref "J6") (pin "POE3") (pinfunction "28_POE3") (pintype "bidirectional"))
      (node (ref "J8") (pin "1") (pinfunction "1_1") (pintype "passive"))
      (node (ref "K1") (pin "2") (pinfunction "2_2") (pintype "bidirectional"))
      (node (ref "K1") (pin "S1") (pinfunction "S1_S1") (pintype "bidirectional"))
      (node (ref "K1") (pin "S2") (pinfunction "S2_S2") (pintype "bidirectional"))
      (node (ref "L3") (pin "2") (pinfunction "2_2") (pintype "passive"))
      (node (ref "R14") (pin "1") (pinfunction "1_1") (pintype "passive"))
      (node (ref "U1") (pin "GND1") (pinfunction "GND1_GND1") (pintype "bidirectional"))
      (node (ref "U1") (pin "GND2") (pinfunction "GND2_GND2") (pintype "bidirectional"))
      (node (ref "U2") (pin "5") (pinfunction "GND_5") (pintype "bidirectional"))
    )
    (net (code "28") (name "I2C_SCL") (class "Default")
      (node (ref "IC2") (pin "19") (pinfunction "PC0(SCL/PCINT16)_19") (pintype "bidirectional"))
      (node (ref "J1") (pin "22") (pinfunction "22_22") (pintype "bidirectional"))
      (node (ref "J5") (pin "4") (pinfunction "4_4") (pintype "passive"))
      (node (ref "J6") (pin "22") (pinfunction "22_22") (pintype "bidirectional"))
      (node (ref "R18") (pin "1") (pinfunction "1_1") (pintype "passive"))
    )
    (net (code "29") (name "I2C_SDA") (class "Default")
      (node (ref "IC2") (pin "20") (pinfunction "PC1(SDA/PCINT17)_20") (pintype "bidirectional"))
      (node (ref "J1") (pin "21") (pinfunction "21_21") (pintype "bidirectional"))
      (node (ref "J5") (pin "3") (pinfunction "3_3") (pintype "passive"))
      (node (ref "J6") (pin "21") (pinfunction "21_21") (pintype "bidirectional"))
      (node (ref "R19") (pin "1") (pinfunction "1_1") (pintype "passive"))
    )
    (net (code "30") (name "LINKLED") (class "Default")
      (node (ref "IC4") (pin "25") (pinfunction "LINKLED_25") (pintype "passive"))
      (node (ref "J1") (pin "8") (pinfunction "8_8") (pintype "bidirectional"))
      (node (ref "J6") (pin "8") (pinfunction "8_8") (pintype "bidirectional"))
      (node (ref "R2") (pin "1") (pinfunction "1_1") (pintype "passive"))
    )
    (net (code "31") (name "MOSI") (class "Default")
      (node (ref "C25") (pin "2") (pinfunction "2_2") (pintype "passive"))
      (node (ref "J1") (pin "25") (pinfunction "25_25") (pintype "bidirectional"))
      (node (ref "J5") (pin "8") (pinfunction "8_8") (pintype "passive"))
      (node (ref "J6") (pin "25") (pinfunction "25_25") (pintype "bidirectional"))
      (node (ref "R16") (pin "1") (pinfunction "1_1") (pintype "passive"))
    )
    (net (code "32") (name "Net-(C3-Pad1)") (class "Default")
      (node (ref "C3") (pin "1") (pinfunction "1_1") (pintype "passive"))
      (node (ref "D1") (pin "C") (pinfunction "C_C") (pintype "passive"))
      (node (ref "D2") (pin "C") (pinfunction "C_C") (pintype "passive"))
      (node (ref "L1") (pin "1") (pinfunction "1_1") (pintype "passive"))
    )
    (net (code "33") (name "Net-(C10-Pad2)") (class "Default")
      (node (ref "C10") (pin "2") (pinfunction "2_2") (pintype "passive"))
      (node (ref "K1") (pin "1") (pinfunction "1_1") (pintype "bidirectional"))
      (node (ref "R12") (pin "2") (pinfunction "2_2") (pintype "passive"))
      (node (ref "R7") (pin "1") (pinfunction "1_1") (pintype "passive"))
    )
    (net (code "34") (name "Net-(C18-Pad2)") (class "Default")
      (node (ref "C18") (pin "2") (pinfunction "2_2") (pintype "passive"))
      (node (ref "J5") (pin "2") (pinfunction "2_2") (pintype "passive"))
      (node (ref "L4") (pin "1") (pinfunction "1_1") (pintype "passive"))
    )
    (net (code "35") (name "Net-(D1-PadA)") (class "Default")
      (node (ref "D1") (pin "A") (pinfunction "A_A") (pintype "passive"))
      (node (ref "J2") (pin "1") (pinfunction "1_1") (pintype "passive"))
    )
    (net (code "36") (name "Net-(D4-AN)") (class "Default")
      (node (ref "C12") (pin "2") (pinfunction "2_2") (pintype "passive"))
      (node (ref "D4") (pin "2") (pinfunction "AN_2") (pintype "passive"))
      (node (ref "F1") (pin "2") (pinfunction "2_2") (pintype "bidirectional"))
    )
    (net (code "37") (name "Net-(D5-BLU)") (class "Default")
      (node (ref "D5") (pin "B") (pinfunction "BLU_B") (pintype "bidirectional"))
      (node (ref "R5") (pin "2") (pinfunction "2_2") (pintype "passive"))
    )
    (net (code "38") (name "Net-(D5-GRN)") (class "Default")
      (node (ref "D5") (pin "G") (pinfunction "GRN_G") (pintype "bidirectional"))
      (node (ref "R6") (pin "2") (pinfunction "2_2") (pintype "passive"))
    )
    (net (code "39") (name "Net-(D5-RED)") (class "Default")
      (node (ref "D5") (pin "R") (pinfunction "RED_R") (pintype "bidirectional"))
      (node (ref "R4") (pin "2") (pinfunction "2_2") (pintype "passive"))
    )
    (net (code "40") (name "Net-(IC1-~{DTR})") (class "Default")
      (node (ref "C15") (pin "1") (pinfunction "1_1") (pintype "passive"))
      (node (ref "IC1") (pin "31") (pinfunction "~{DTR}_31") (pintype "output"))
    )
    (net (code "41") (name "Net-(IC2-AREF)") (class "Default")
      (node (ref "IC2") (pin "29") (pinfunction "AREF_29") (pintype "bidirectional"))
      (node (ref "J12") (pin "1") (pinfunction "5_1") (pintype "passive"))
    )
    (net (code "42") (name "Net-(IC2-XTAL1)") (class "Default")
      (node (ref "C17") (pin "2") (pinfunction "2_2") (pintype "passive"))
      (node (ref "IC2") (pin "8") (pinfunction "XTAL1_8") (pintype "bidirectional"))
      (node (ref "R13") (pin "1") (pinfunction "1_1") (pintype "passive"))
      (node (ref "Y1") (pin "1") (pinfunction "1_1") (pintype "passive"))
    )
    (net (code "43") (name "Net-(IC2-XTAL2)") (class "Default")
      (node (ref "C16") (pin "2") (pinfunction "2_2") (pintype "passive"))
      (node (ref "IC2") (pin "7") (pinfunction "XTAL2_7") (pintype "bidirectional"))
      (node (ref "R13") (pin "2") (pinfunction "2_2") (pintype "passive"))
      (node (ref "Y1") (pin "2") (pinfunction "2_2") (pintype "passive"))
    )
    (net (code "44") (name "Net-(IC4-1V2O)") (class "Default")
      (node (ref "C20") (pin "1") (pinfunction "1_1") (pintype "passive"))
      (node (ref "IC4") (pin "22") (pinfunction "1V2O_22") (pintype "passive"))
    )
    (net (code "45") (name "Net-(IC4-EXRES1)") (class "Default")
      (node (ref "IC4") (pin "10") (pinfunction "EXRES1_10") (pintype "passive"))
      (node (ref "R14") (pin "2") (pinfunction "2_2") (pintype "passive"))
    )
    (net (code "46") (name "Net-(IC4-INT_N)") (class "Default")
      (node (ref "IC4") (pin "36") (pinfunction "INT_N_36") (pintype "passive"))
      (node (ref "J9") (pin "1") (pinfunction "5_1") (pintype "passive"))
    )
    (net (code "47") (name "Net-(IC4-TOCAP)") (class "Default")
      (node (ref "C21") (pin "1") (pinfunction "1_1") (pintype "passive"))
      (node (ref "IC4") (pin "20") (pinfunction "TOCAP_20") (pintype "passive"))
    )
    (net (code "48") (name "Net-(IC4-XI{slash}CLKIN)") (class "Default")
      (node (ref "C28") (pin "2") (pinfunction "2_2") (pintype "passive"))
      (node (ref "IC4") (pin "30") (pinfunction "XI/CLKIN_30") (pintype "passive"))
      (node (ref "R20") (pin "2") (pinfunction "2_2") (pintype "passive"))
      (node (ref "Y2") (pin "2") (pinfunction "2_2") (pintype "passive"))
    )
    (net (code "49") (name "Net-(IC4-XO)") (class "Default")
      (node (ref "C27") (pin "2") (pinfunction "2_2") (pintype "passive"))
      (node (ref "IC4") (pin "31") (pinfunction "XO_31") (pintype "passive"))
      (node (ref "R20") (pin "1") (pinfunction "1_1") (pintype "passive"))
      (node (ref "Y2") (pin "1") (pinfunction "1_1") (pintype "passive"))
    )
    (net (code "50") (name "Net-(J1-27)") (class "Default")
      (node (ref "C4") (pin "1") (pinfunction "1_1") (pintype "passive"))
      (node (ref "C5") (pin "1") (pinfunction "1_1") (pintype "passive"))
      (node (ref "J1") (pin "POE1_S") (pinfunction "27_POE1_S") (pintype "bidirectional"))
      (node (ref "L2") (pin "1") (pinfunction "1_1") (pintype "passive"))
    )
    (net (code "51") (name "Net-(L3-Pad1)") (class "Default")
      (node (ref "L3") (pin "1") (pinfunction "1_1") (pintype "passive"))
      (node (ref "U2") (pin "S1") (pinfunction "GND_S1") (pintype "bidirectional"))
      (node (ref "U2") (pin "S2") (pinfunction "GND_S2") (pintype "bidirectional"))
      (node (ref "U2") (pin "S3") (pinfunction "GND_S3") (pintype "bidirectional"))
      (node (ref "U2") (pin "S4") (pinfunction "GND_S4") (pintype "bidirectional"))
      (node (ref "U2") (pin "S5") (pinfunction "GND_S5") (pintype "bidirectional"))
      (node (ref "U2") (pin "S6") (pinfunction "GND_S6") (pintype "bidirectional"))
      (node (ref "Z1") (pin "2") (pinfunction "2_2") (pintype "passive"))
      (node (ref "Z2") (pin "2") (pinfunction "2_2") (pintype "passive"))
    )
    (net (code "52") (name "Net-(RN1B-1)") (class "Default")
      (node (ref "RN1") (pin "2") (pinfunction "1_2") (pintype "passive"))
      (node (ref "RN2") (pin "3") (pinfunction "1_3") (pintype "passive"))
      (node (ref "U1") (pin "P$5") (pinfunction "TX+_P$5") (pintype "bidirectional"))
    )
    (net (code "53") (name "Net-(RN1C-1)") (class "Default")
      (node (ref "C7") (pin "1") (pinfunction "1_1") (pintype "passive"))
      (node (ref "RN1") (pin "3") (pinfunction "1_3") (pintype "passive"))
      (node (ref "RN2") (pin "2") (pinfunction "1_2") (pintype "passive"))
    )
    (net (code "54") (name "Net-(RN1D-1)") (class "Default")
      (node (ref "C6") (pin "1") (pinfunction "1_1") (pintype "passive"))
      (node (ref "RN1") (pin "4") (pinfunction "1_4") (pintype "passive"))
      (node (ref "RN2") (pin "1") (pinfunction "1_1") (pintype "passive"))
    )
    (net (code "55") (name "Net-(RN2A-2)") (class "Default")
      (node (ref "C9") (pin "2") (pinfunction "2_2") (pintype "passive"))
      (node (ref "RN2") (pin "7") (pinfunction "2_7") (pintype "passive"))
      (node (ref "RN2") (pin "8") (pinfunction "2_8") (pintype "passive"))
      (node (ref "U1") (pin "P$3") (pinfunction "RXCT_P$3") (pintype "bidirectional"))
    )
    (net (code "56") (name "Net-(RN2D-1)") (class "Default")
      (node (ref "RN1") (pin "1") (pinfunction "1_1") (pintype "passive"))
      (node (ref "RN2") (pin "4") (pinfunction "1_4") (pintype "passive"))
      (node (ref "U1") (pin "P$6") (pinfunction "TX-_P$6") (pintype "bidirectional"))
    )
    (net (code "57") (name "Net-(U1-G-)") (class "Default")
      (node (ref "R3") (pin "2") (pinfunction "2_2") (pintype "passive"))
      (node (ref "U1") (pin "P$14") (pinfunction "G-_P$14") (pintype "bidirectional"))
    )
    (net (code "58") (name "Net-(U1-RX+)") (class "Default")
      (node (ref "C6") (pin "2") (pinfunction "2_2") (pintype "passive"))
      (node (ref "U1") (pin "P$1") (pinfunction "RX+_P$1") (pintype "bidirectional"))
    )
    (net (code "59") (name "Net-(U1-RX-)") (class "Default")
      (node (ref "C7") (pin "2") (pinfunction "2_2") (pintype "passive"))
      (node (ref "U1") (pin "P$2") (pinfunction "RX-_P$2") (pintype "bidirectional"))
    )
    (net (code "60") (name "Net-(U1-TXCT)") (class "Default")
      (node (ref "C8") (pin "2") (pinfunction "2_2") (pintype "passive"))
      (node (ref "R1") (pin "1") (pinfunction "1_1") (pintype "passive"))
      (node (ref "U1") (pin "P$4") (pinfunction "TXCT_P$4") (pintype "bidirectional"))
    )
    (net (code "61") (name "Net-(U1-V+)") (class "Default")
      (node (ref "D3") (pin "C") (pinfunction "C_C") (pintype "passive"))
      (node (ref "GND/POE-/POE+") (pin "3") (pinfunction "3_3") (pintype "passive"))
      (node (ref "U1") (pin "P$9") (pinfunction "V+_P$9") (pintype "bidirectional"))
    )
    (net (code "62") (name "Net-(U1-V-)") (class "Default")
      (node (ref "D3") (pin "A") (pinfunction "A_A") (pintype "passive"))
      (node (ref "GND/POE-/POE+") (pin "2") (pinfunction "2_2") (pintype "passive"))
      (node (ref "U1") (pin "P$10") (pinfunction "V-_P$10") (pintype "bidirectional"))
    )
    (net (code "63") (name "Net-(U1-Y-)") (class "Default")
      (node (ref "R2") (pin "2") (pinfunction "2_2") (pintype "passive"))
      (node (ref "U1") (pin "P$12") (pinfunction "Y-_P$12") (pintype "bidirectional"))
    )
    (net (code "64") (name "Net-(U2-DM)") (class "Default")
      (node (ref "R11") (pin "2") (pinfunction "2_2") (pintype "passive"))
      (node (ref "U2") (pin "2") (pinfunction "DM_2") (pintype "bidirectional"))
      (node (ref "Z2") (pin "1") (pinfunction "1_1") (pintype "passive"))
    )
    (net (code "65") (name "Net-(U2-DP)") (class "Default")
      (node (ref "R10") (pin "2") (pinfunction "2_2") (pintype "passive"))
      (node (ref "U2") (pin "3") (pinfunction "DP_3") (pintype "bidirectional"))
      (node (ref "Z1") (pin "1") (pinfunction "1_1") (pintype "passive"))
    )
    (net (code "66") (name "Net-(U2-VCC)") (class "Default")
      (node (ref "F1") (pin "1") (pinfunction "1_1") (pintype "bidirectional"))
      (node (ref "U2") (pin "1") (pinfunction "VCC_1") (pintype "bidirectional"))
    )
    (net (code "67") (name "RD+") (class "Default")
      (node (ref "IC1") (pin "14") (pinfunction "USBDP_14") (pintype "bidirectional"))
      (node (ref "R10") (pin "1") (pinfunction "1_1") (pintype "passive"))
    )
    (net (code "68") (name "RD-") (class "Default")
      (node (ref "IC1") (pin "15") (pinfunction "USBDM_15") (pintype "bidirectional"))
      (node (ref "R11") (pin "1") (pinfunction "1_1") (pintype "passive"))
    )
    (net (code "69") (name "RESET") (class "Default")
      (node (ref "C10") (pin "1") (pinfunction "1_1") (pintype "passive"))
      (node (ref "C15") (pin "2") (pinfunction "2_2") (pintype "passive"))
      (node (ref "IC2") (pin "4") (pinfunction "~{RESET}_4") (pintype "bidirectional"))
      (node (ref "IC3") (pin "3") (pinfunction "/MR_3") (pintype "input"))
      (node (ref "J1") (pin "17") (pinfunction "17_17") (pintype "bidirectional"))
      (node (ref "J6") (pin "17") (pinfunction "17_17") (pintype "bidirectional"))
      (node (ref "R15") (pin "1") (pinfunction "1_1") (pintype "passive"))
    )
    (net (code "70") (name "RXIN") (class "Default")
      (node (ref "IC4") (pin "5") (pinfunction "RXN_5") (pintype "passive"))
      (node (ref "J1") (pin "13") (pinfunction "13_13") (pintype "bidirectional"))
      (node (ref "J6") (pin "13") (pinfunction "13_13") (pintype "bidirectional"))
      (node (ref "RN1") (pin "6") (pinfunction "2_6") (pintype "passive"))
    )
    (net (code "71") (name "RXIP") (class "Default")
      (node (ref "IC4") (pin "6") (pinfunction "RXP_6") (pintype "passive"))
      (node (ref "J1") (pin "14") (pinfunction "14_14") (pintype "bidirectional"))
      (node (ref "J6") (pin "14") (pinfunction "14_14") (pintype "bidirectional"))
      (node (ref "RN1") (pin "5") (pinfunction "2_5") (pintype "passive"))
    )
    (net (code "72") (name "SCLK") (class "Default")
      (node (ref "C26") (pin "2") (pinfunction "2_2") (pintype "passive"))
      (node (ref "J1") (pin "24") (pinfunction "24_24") (pintype "bidirectional"))
      (node (ref "J5") (pin "7") (pinfunction "7_7") (pintype "passive"))
      (node (ref "J6") (pin "24") (pinfunction "24_24") (pintype "bidirectional"))
      (node (ref "R17") (pin "1") (pinfunction "1_1") (pintype "passive"))
    )
    (net (code "73") (name "TXON") (class "Default")
      (node (ref "IC4") (pin "1") (pinfunction "TXN_1") (pintype "passive"))
      (node (ref "J1") (pin "10") (pinfunction "10_10") (pintype "bidirectional"))
      (node (ref "J6") (pin "10") (pinfunction "10_10") (pintype "bidirectional"))
      (node (ref "RN1") (pin "8") (pinfunction "2_8") (pintype "passive"))
    )
    (net (code "74") (name "TXOP") (class "Default")
      (node (ref "IC4") (pin "2") (pinfunction "TXP_2") (pintype "passive"))
      (node (ref "J1") (pin "11") (pinfunction "11_11") (pintype "bidirectional"))
      (node (ref "J6") (pin "11") (pinfunction "11_11") (pintype "bidirectional"))
      (node (ref "RN1") (pin "7") (pinfunction "2_7") (pintype "passive"))
    )
    (net (code "75") (name "USBRXD") (class "Default")
      (node (ref "IC1") (pin "30") (pinfunction "TXD_30") (pintype "output"))
      (node (ref "R9") (pin "1") (pinfunction "1_1") (pintype "passive"))
    )
    (net (code "76") (name "USBTXD") (class "Default")
      (node (ref "IC1") (pin "2") (pinfunction "RXD_2") (pintype "input"))
      (node (ref "R8") (pin "1") (pinfunction "1_1") (pintype "passive"))
    )
    (net (code "77") (name "USBVCC") (class "Default")
      (node (ref "D4") (pin "1") (pinfunction "CA_1") (pintype "passive"))
      (node (ref "J3") (pin "2") (pinfunction "2_2") (pintype "passive"))
    )
    (net (code "78") (name "VIN") (class "Default")
      (node (ref "C1") (pin "+") (pinfunction "+_+") (pintype "passive"))
      (node (ref "C2") (pin "1") (pinfunction "1_1") (pintype "passive"))
      (node (ref "C31") (pin "1") (pinfunction "1_1") (pintype "passive"))
      (node (ref "D6") (pin "1") (pinfunction "CA_1") (pintype "passive"))
      (node (ref "IC5") (pin "P$1") (pinfunction "VIN_P$1") (pintype "bidirectional"))
      (node (ref "J1") (pin "2") (pinfunction "2_2") (pintype "bidirectional"))
      (node (ref "J6") (pin "2") (pinfunction "2_2") (pintype "bidirectional"))
      (node (ref "L1") (pin "2") (pinfunction "2_2") (pintype "passive"))
      (node (ref "L2") (pin "2") (pinfunction "2_2") (pintype "passive"))
    )
    (net (code "79") (name "WIZRST") (class "Default")
      (node (ref "IC3") (pin "2") (pinfunction "/RESET_2") (pintype "output"))
      (node (ref "IC4") (pin "37") (pinfunction "RST_N_37") (pintype "passive"))
    )
    (net (code "80") (name "unconnected-(IC1-3V3OUT-Pad16)") (class "Default")
      (node (ref "IC1") (pin "16") (pinfunction "3V3OUT_16") (pintype "output"))
    )
    (net (code "81") (name "unconnected-(IC1-CBUS0-Pad22)") (class "Default")
      (node (ref "IC1") (pin "22") (pinfunction "CBUS0_22") (pintype "bidirectional"))
    )
    (net (code "82") (name "unconnected-(IC1-CBUS1-Pad21)") (class "Default")
      (node (ref "IC1") (pin "21") (pinfunction "CBUS1_21") (pintype "bidirectional"))
    )
    (net (code "83") (name "unconnected-(IC1-CBUS2-Pad10)") (class "Default")
      (node (ref "IC1") (pin "10") (pinfunction "CBUS2_10") (pintype "bidirectional"))
    )
    (net (code "84") (name "unconnected-(IC1-CBUS3-Pad11)") (class "Default")
      (node (ref "IC1") (pin "11") (pinfunction "CBUS3_11") (pintype "bidirectional"))
    )
    (net (code "85") (name "unconnected-(IC1-CBUS4-Pad9)") (class "Default")
      (node (ref "IC1") (pin "9") (pinfunction "CBUS4_9") (pintype "bidirectional"))
    )
    (net (code "86") (name "unconnected-(IC1-OSCI-Pad27)") (class "Default")
      (node (ref "IC1") (pin "27") (pinfunction "OSCI_27") (pintype "input"))
    )
    (net (code "87") (name "unconnected-(IC1-OSCO-Pad28)") (class "Default")
      (node (ref "IC1") (pin "28") (pinfunction "OSCO_28") (pintype "output"))
    )
    (net (code "88") (name "unconnected-(IC1-~{CTS}-Pad8)") (class "Default")
      (node (ref "IC1") (pin "8") (pinfunction "~{CTS}_8") (pintype "input"))
    )
    (net (code "89") (name "unconnected-(IC1-~{DCD}-Pad7)") (class "Default")
      (node (ref "IC1") (pin "7") (pinfunction "~{DCD}_7") (pintype "input"))
    )
    (net (code "90") (name "unconnected-(IC1-~{DSR}-Pad6)") (class "Default")
      (node (ref "IC1") (pin "6") (pinfunction "~{DSR}_6") (pintype "input"))
    )
    (net (code "91") (name "unconnected-(IC1-~{RESET}-Pad18)") (class "Default")
      (node (ref "IC1") (pin "18") (pinfunction "~{RESET}_18") (pintype "input"))
    )
    (net (code "92") (name "unconnected-(IC1-~{RI}-Pad3)") (class "Default")
      (node (ref "IC1") (pin "3") (pinfunction "~{RI}_3") (pintype "input"))
    )
    (net (code "93") (name "unconnected-(IC1-~{RTS}-Pad32)") (class "Default")
      (node (ref "IC1") (pin "32") (pinfunction "~{RTS}_32") (pintype "output"))
    )
    (net (code "94") (name "unconnected-(IC2-PA1(ADC1{slash}PCINT1)-Pad36)") (class "Default")
      (node (ref "IC2") (pin "36") (pinfunction "PA1(ADC1/PCINT1)_36") (pintype "bidirectional"))
    )
    (net (code "95") (name "unconnected-(IC2-PA5(ADC5{slash}PCINT5)-Pad32)") (class "Default")
      (node (ref "IC2") (pin "32") (pinfunction "PA5(ADC5/PCINT5)_32") (pintype "bidirectional"))
    )
    (net (code "96") (name "unconnected-(IC2-PA6(ADC6{slash}PCINT6)-Pad31)") (class "Default")
      (node (ref "IC2") (pin "31") (pinfunction "PA6(ADC6/PCINT6)_31") (pintype "bidirectional"))
    )
    (net (code "97") (name "unconnected-(IC2-PA7(ADC7{slash}PCINT7)-Pad30)") (class "Default")
      (node (ref "IC2") (pin "30") (pinfunction "PA7(ADC7/PCINT7)_30") (pintype "bidirectional"))
    )
    (net (code "98") (name "unconnected-(IC2-PB0(PCINT8{slash}XCK0{slash}T0)-Pad40)") (class "Default")
      (node (ref "IC2") (pin "40") (pinfunction "PB0(PCINT8/XCK0/T0)_40") (pintype "bidirectional"))
    )
    (net (code "99") (name "unconnected-(IC2-PB1(PCINT9{slash}CLKO{slash}T1)-Pad41)") (class "Default")
      (node (ref "IC2") (pin "41") (pinfunction "PB1(PCINT9/CLKO/T1)_41") (pintype "bidirectional"))
    )
    (net (code "100") (name "unconnected-(IC2-PC6(TOSC1{slash}PCINT22)-Pad25)") (class "Default")
      (node (ref "IC2") (pin "25") (pinfunction "PC6(TOSC1/PCINT22)_25") (pintype "bidirectional"))
    )
    (net (code "101") (name "unconnected-(IC2-PC7(TOSC2{slash}PCINT23)-Pad26)") (class "Default")
      (node (ref "IC2") (pin "26") (pinfunction "PC7(TOSC2/PCINT23)_26") (pintype "bidirectional"))
    )
    (net (code "102") (name "unconnected-(IC4-DNC-Pad7)") (class "Default")
      (node (ref "IC4") (pin "7") (pinfunction "DNC_7") (pintype "passive"))
    )
    (net (code "103") (name "unconnected-(IC4-DUPLED-Pad26)") (class "Default")
      (node (ref "IC4") (pin "26") (pinfunction "DUPLED_26") (pintype "passive"))
    )
    (net (code "104") (name "unconnected-(IC4-NC-Pad12)") (class "Default")
      (node (ref "IC4") (pin "12") (pinfunction "NC_12") (pintype "passive"))
    )
    (net (code "105") (name "unconnected-(IC4-NC-Pad13)") (class "Default")
      (node (ref "IC4") (pin "13") (pinfunction "NC_13") (pintype "passive"))
    )
    (net (code "106") (name "unconnected-(IC4-NC-Pad46)") (class "Default")
      (node (ref "IC4") (pin "46") (pinfunction "NC_46") (pintype "passive"))
    )
    (net (code "107") (name "unconnected-(IC4-NC-Pad47)") (class "Default")
      (node (ref "IC4") (pin "47") (pinfunction "NC_47") (pintype "passive"))
    )
    (net (code "108") (name "unconnected-(IC4-PMODE0-Pad45)") (class "Default")
      (node (ref "IC4") (pin "45") (pinfunction "PMODE0_45") (pintype "passive"))
    )
    (net (code "109") (name "unconnected-(IC4-PMODE1-Pad44)") (class "Default")
      (node (ref "IC4") (pin "44") (pinfunction "PMODE1_44") (pintype "passive"))
    )
    (net (code "110") (name "unconnected-(IC4-PMODE2-Pad43)") (class "Default")
      (node (ref "IC4") (pin "43") (pinfunction "PMODE2_43") (pintype "passive"))
    )
    (net (code "111") (name "unconnected-(IC4-RSVD-Pad23)") (class "Default")
      (node (ref "IC4") (pin "23") (pinfunction "RSVD_23") (pintype "passive"))
    )
    (net (code "112") (name "unconnected-(IC4-RSVD-Pad38)") (class "Default")
      (node (ref "IC4") (pin "38") (pinfunction "RSVD_38") (pintype "passive"))
    )
    (net (code "113") (name "unconnected-(IC4-RSVD-Pad39)") (class "Default")
      (node (ref "IC4") (pin "39") (pinfunction "RSVD_39") (pintype "passive"))
    )
    (net (code "114") (name "unconnected-(IC4-RSVD-Pad40)") (class "Default")
      (node (ref "IC4") (pin "40") (pinfunction "RSVD_40") (pintype "passive"))
    )
    (net (code "115") (name "unconnected-(IC4-RSVD-Pad41)") (class "Default")
      (node (ref "IC4") (pin "41") (pinfunction "RSVD_41") (pintype "passive"))
    )
    (net (code "116") (name "unconnected-(IC4-RSVD-Pad42)") (class "Default")
      (node (ref "IC4") (pin "42") (pinfunction "RSVD_42") (pintype "passive"))
    )
    (net (code "117") (name "unconnected-(IC4-SPDLED-Pad24)") (class "Default")
      (node (ref "IC4") (pin "24") (pinfunction "SPDLED_24") (pintype "passive"))
    )
    (net (code "118") (name "unconnected-(IC4-VBG-Pad18)") (class "Default")
      (node (ref "IC4") (pin "18") (pinfunction "VBG_18") (pintype "passive"))
    )
    (net (code "119") (name "unconnected-(J5-Pad6)") (class "Default")
      (node (ref "J5") (pin "6") (pinfunction "6_6") (pintype "passive"))
    )
    (net (code "120") (name "unconnected-(J6-27-PadPOE1)") (class "Default")
      (node (ref "J6") (pin "POE1") (pinfunction "27_POE1") (pintype "bidirectional"))
    )
    (net (code "121") (name "unconnected-(U2-ID-Pad4)") (class "Default")
      (node (ref "U2") (pin "4") (pinfunction "ID_4") (pintype "bidirectional"))
    )
  )
)
